# 5V_buck.net
KiCad netlist of a schematic drawn in Altium Designer
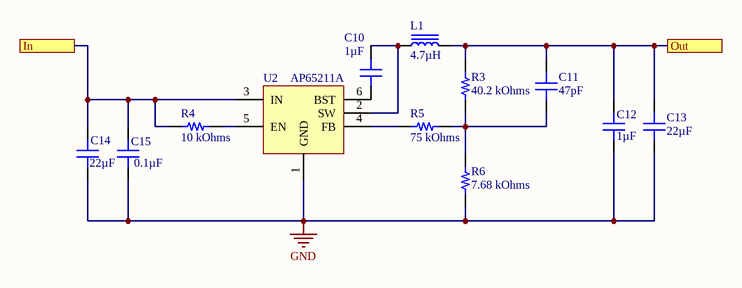
[diagram p0: 5V_buck.SchDoc]

(export (version "E")
  (design (tool "Eeschema 10.0.6"))
  (components
    (comp (ref "C10")
      (value "1µF")
      (footprint "CAP 0603_1608")
      (description "CAP CER 1UF 25V X7R 0603")
      (fields
        (field (name "PART NUMBER") "GCJ188R71E105KA01D")
        (field (name "MANUFACTURER") "Murata Electronics")
      )
      (libsource (lib "Celestial Altium Library - altium_library") (part "Capacitor"))
    )
    (comp (ref "C11")
      (value "47pF")
      (footprint "CAP 0603_1608")
      (description "CAP CER 47PF 100V NP0 0603")
      (fields
        (field (name "PART NUMBER") "C1608NP02A470J080AA")
        (field (name "MANUFACTURER") "TDK Corporation")
      )
      (libsource (lib "Celestial Altium Library - altium_library") (part "Capacitor"))
    )
    (comp (ref "C12")
      (value "1µF")
      (footprint "CAP 0603_1608")
      (description "CAP CER 1UF 25V X7R 0603")
      (fields
        (field (name "PART NUMBER") "GCJ188R71E105KA01D")
        (field (name "MANUFACTURER") "Murata Electronics")
      )
      (libsource (lib "Celestial Altium Library - altium_library") (part "Capacitor"))
    )
    (comp (ref "C13")
      (value "22µF")
      (footprint "CAP 0805_2012")
      (description "CAP CER 22UF 16V X5R 0805")
      (fields
        (field (name "PART NUMBER") "CL21A226MOQNNNE")
        (field (name "MANUFACTURER") "Samsung Electro-Mechanics")
      )
      (libsource (lib "Celestial Altium Library - altium_library") (part "Capacitor"))
    )
    (comp (ref "C14")
      (value "22µF")
      (footprint "CAP 0805_2012")
      (description "CAP CER 10UF 25V X7S 0805")
      (fields
        (field (name "PART NUMBER") "C2012X7S1E106K125AC")
        (field (name "MANUFACTURER") "TDK Corporation")
      )
      (libsource (lib "Celestial Altium Library - altium_library") (part "Capacitor"))
    )
    (comp (ref "C15")
      (value "0.1µF")
      (footprint "CAP 0603_1608")
      (description "CAP CER 0.1UF 100V 0603 EPOXY")
      (fields
        (field (name "PART NUMBER") "GCG188R92A104KA03D")
        (field (name "MANUFACTURER") "Murata Electronics")
      )
      (libsource (lib "Celestial Altium Library - altium_library") (part "Capacitor"))
    )
    (comp (ref "L1")
      (value "4.7µH")
      (footprint "IND 1008_2520")
      (description "FIXED IND 4.7UH 1A 110 MOHM SMD")
      (fields (field (name "PART NUMBER") "MLP2520S4R7ST0S1") (field (name "MANUFACTURER") "TDK Corporation"))
      (libsource (lib "Celestial Altium Library - altium_library") (part "Inductor"))
    )
    (comp (ref "R3")
      (value "40.2 kOhms")
      (footprint "RES 0603_1608")
      (description "RES SMD 40.2KOHM 0.5% 1/10W 0603")
      (fields (field (name "PART NUMBER") "RT0603DRD0740K2L") (field (name "MANUFACTURER") "Yageo"))
      (libsource (lib "Celestial Altium Library - altium_library") (part "Resistor"))
    )
    (comp (ref "R4")
      (value "10 kOhms")
      (footprint "RES 0603_1608")
      (description "RES 10K OHM 0.1% 1/16W 0603")
      (fields
        (field (name "PART NUMBER") "RNCS0603BKE10K0")
        (field (name "MANUFACTURER") "Stackpole Electronics Inc")
      )
      (libsource (lib "Celestial Altium Library - altium_library") (part "Resistor"))
    )
    (comp (ref "R5")
      (value "75 kOhms")
      (footprint "RES 0603_1608")
      (description "RES SMD 75K OHM 5% 1/10W 0603")
      (fields (field (name "PART NUMBER") "CR0603-JW-753ELF") (field (name "MANUFACTURER") "Bourns Inc."))
      (libsource (lib "Celestial Altium Library - altium_library") (part "Resistor"))
    )
    (comp (ref "R6")
      (value "7.68 kOhms")
      (footprint "RES 0603_1608")
      (description "RES 7.68K OHM 1% 1/10W 0603")
      (fields
        (field (name "PART NUMBER") "RMCF0603FT7K68")
        (field (name "MANUFACTURER") "Stackpole Electronics Inc")
      )
      (libsource (lib "Celestial Altium Library - altium_library") (part "Resistor"))
    )
    (comp (ref "U2")
      (value "AP65211A")
      (footprint "TSOT-26-6")
      (description "ADJ step down Buck")
      (libsource (lib "IC") (part "AP65211A"))
    )
  )
  (nets
    (net (code "1") (name "/In") (class "Default")
      (node (ref "C14") (pin "2") (pinfunction "2_2") (pintype "passive"))
      (node (ref "C15") (pin "1") (pinfunction "1_1") (pintype "passive"))
      (node (ref "R4") (pin "2") (pinfunction "2_2") (pintype "passive"))
      (node (ref "U2") (pin "3") (pinfunction "IN_3") (pintype "passive"))
    )
    (net (code "2") (name "/Out") (class "Default")
      (node (ref "C11") (pin "2") (pinfunction "2_2") (pintype "passive"))
      (node (ref "C12") (pin "2") (pinfunction "2_2") (pintype "passive"))
      (node (ref "C13") (pin "2") (pinfunction "2_2") (pintype "passive"))
      (node (ref "L1") (pin "2") (pinfunction "2_2") (pintype "passive"))
      (node (ref "R3") (pin "2") (pinfunction "2_2") (pintype "passive"))
    )
    (net (code "3") (name "GND") (class "Default")
      (node (ref "C12") (pin "1") (pinfunction "1_1") (pintype "passive"))
      (node (ref "C13") (pin "1") (pinfunction "1_1") (pintype "passive"))
      (node (ref "C14") (pin "1") (pinfunction "1_1") (pintype "passive"))
      (node (ref "C15") (pin "2") (pinfunction "2_2") (pintype "passive"))
      (node (ref "R6") (pin "1") (pinfunction "1_1") (pintype "passive"))
      (node (ref "U2") (pin "1") (pinfunction "GND_1") (pintype "passive"))
    )
    (net (code "4") (name "Net-(C11-Pad1)") (class "Default")
      (node (ref "C11") (pin "1") (pinfunction "1_1") (pintype "passive"))
      (node (ref "R3") (pin "1") (pinfunction "1_1") (pintype "passive"))
      (node (ref "R5") (pin "2") (pinfunction "2_2") (pintype "passive"))
      (node (ref "R6") (pin "2") (pinfunction "2_2") (pintype "passive"))
    )
    (net (code "5") (name "Net-(U2-BST)") (class "Default")
      (node (ref "C10") (pin "2") (pinfunction "2_2") (pintype "passive"))
      (node (ref "U2") (pin "6") (pinfunction "BST_6") (pintype "passive"))
    )
    (net (code "6") (name "Net-(U2-EN)") (class "Default")
      (node (ref "R4") (pin "1") (pinfunction "1_1") (pintype "passive"))
      (node (ref "U2") (pin "5") (pinfunction "EN_5") (pintype "passive"))
    )
    (net (code "7") (name "Net-(U2-FB)") (class "Default")
      (node (ref "R5") (pin "1") (pinfunction "1_1") (pintype "passive"))
      (node (ref "U2") (pin "4") (pinfunction "FB_4") (pintype "passive"))
    )
    (net (code "8") (name "Net-(U2-SW)") (class "Default")
      (node (ref "C10") (pin "1") (pinfunction "1_1") (pintype "passive"))
      (node (ref "L1") (pin "1") (pinfunction "1_1") (pintype "passive"))
      (node (ref "U2") (pin "2") (pinfunction "SW_2") (pintype "passive"))
    )
  )
)
